# Adapter_-_Stacking_2_wire_CRY8EI.net
KiCad netlist of a schematic drawn in EAGLE
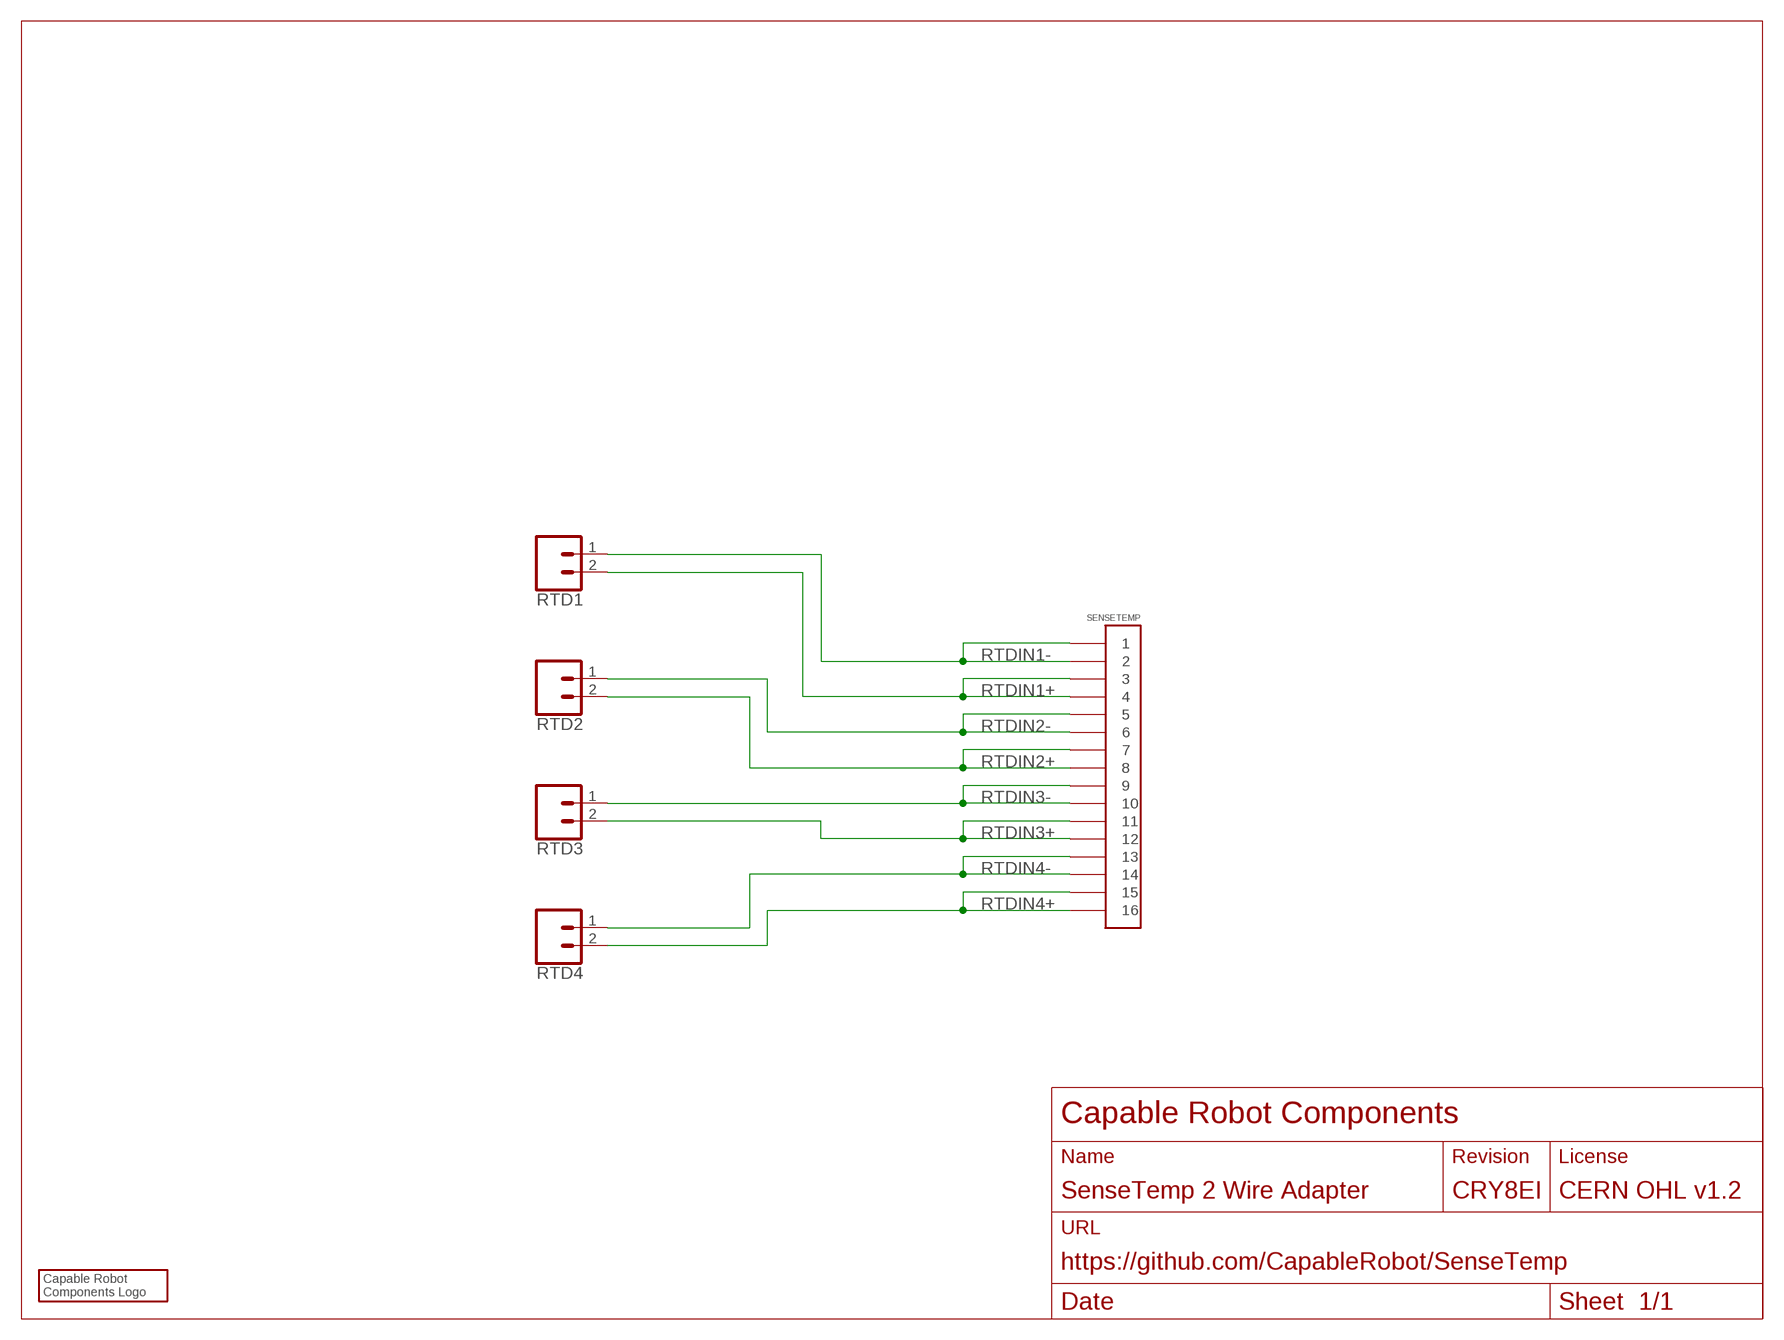
[diagram p0: schematic, sheet 1]

(export (version "E")
  (design (tool "Eeschema 10.0.6"))
  (components
    (comp (ref "LOGO1")
      (value "CRC-LOGO7SILK")
      (footprint "eagle-import:CRC-LOGO-7-SILK")
      (libsource (lib "eagle-import") (part "CRC-LOGO7SILK"))
    )
    (comp (ref "RTD1")
      (value "CONN_025MM")
      (footprint "eagle-import:SCREWTERMINAL-5MM-2")
      (libsource (lib "eagle-import") (part "CONN_025MM"))
    )
    (comp (ref "RTD2")
      (value "CONN_025MM")
      (footprint "eagle-import:SCREWTERMINAL-5MM-2")
      (libsource (lib "eagle-import") (part "CONN_025MM"))
    )
    (comp (ref "RTD3")
      (value "CONN_025MM")
      (footprint "eagle-import:SCREWTERMINAL-5MM-2")
      (libsource (lib "eagle-import") (part "CONN_025MM"))
    )
    (comp (ref "RTD4")
      (value "CONN_025MM")
      (footprint "eagle-import:SCREWTERMINAL-5MM-2")
      (libsource (lib "eagle-import") (part "CONN_025MM"))
    )
    (comp (ref "SENSETEMP")
      (value "CONN-16ZT")
      (footprint "eagle-import:CONN-2X8-050-SMT-ZT")
      (fields (field (name "MPN") "3221-16-0300-00"))
      (libsource (lib "eagle-import") (part "CONN-16ZT"))
    )
  )
  (nets
    (net (code "1") (name "/RTDIN1+") (class "Default")
      (node (ref "RTD1") (pin "2") (pinfunction "2_2") (pintype "passive"))
      (node (ref "SENSETEMP") (pin "3") (pinfunction "3_3") (pintype "bidirectional"))
      (node (ref "SENSETEMP") (pin "4") (pinfunction "4_4") (pintype "bidirectional"))
    )
    (net (code "2") (name "/RTDIN1-") (class "Default")
      (node (ref "RTD1") (pin "1") (pinfunction "1_1") (pintype "passive"))
      (node (ref "SENSETEMP") (pin "1") (pinfunction "1_1") (pintype "bidirectional"))
      (node (ref "SENSETEMP") (pin "2") (pinfunction "2_2") (pintype "bidirectional"))
    )
    (net (code "3") (name "/RTDIN2+") (class "Default")
      (node (ref "RTD2") (pin "2") (pinfunction "2_2") (pintype "passive"))
      (node (ref "SENSETEMP") (pin "7") (pinfunction "7_7") (pintype "bidirectional"))
      (node (ref "SENSETEMP") (pin "8") (pinfunction "8_8") (pintype "bidirectional"))
    )
    (net (code "4") (name "/RTDIN2-") (class "Default")
      (node (ref "RTD2") (pin "1") (pinfunction "1_1") (pintype "passive"))
      (node (ref "SENSETEMP") (pin "5") (pinfunction "5_5") (pintype "bidirectional"))
      (node (ref "SENSETEMP") (pin "6") (pinfunction "6_6") (pintype "bidirectional"))
    )
    (net (code "5") (name "/RTDIN3+") (class "Default")
      (node (ref "RTD3") (pin "2") (pinfunction "2_2") (pintype "passive"))
      (node (ref "SENSETEMP") (pin "11") (pinfunction "11_11") (pintype "bidirectional"))
      (node (ref "SENSETEMP") (pin "12") (pinfunction "12_12") (pintype "bidirectional"))
    )
    (net (code "6") (name "/RTDIN3-") (class "Default")
      (node (ref "RTD3") (pin "1") (pinfunction "1_1") (pintype "passive"))
      (node (ref "SENSETEMP") (pin "10") (pinfunction "10_10") (pintype "bidirectional"))
      (node (ref "SENSETEMP") (pin "9") (pinfunction "9_9") (pintype "bidirectional"))
    )
    (net (code "7") (name "/RTDIN4+") (class "Default")
      (node (ref "RTD4") (pin "2") (pinfunction "2_2") (pintype "passive"))
      (node (ref "SENSETEMP") (pin "15") (pinfunction "15_15") (pintype "bidirectional"))
      (node (ref "SENSETEMP") (pin "16") (pinfunction "16_16") (pintype "bidirectional"))
    )
    (net (code "8") (name "/RTDIN4-") (class "Default")
      (node (ref "RTD4") (pin "1") (pinfunction "1_1") (pintype "passive"))
      (node (ref "SENSETEMP") (pin "13") (pinfunction "13_13") (pintype "bidirectional"))
      (node (ref "SENSETEMP") (pin "14") (pinfunction "14_14") (pintype "bidirectional"))
    )
  )
)
